# 25-Power-CPU.net
KiCad netlist of a schematic drawn in Altium Designer
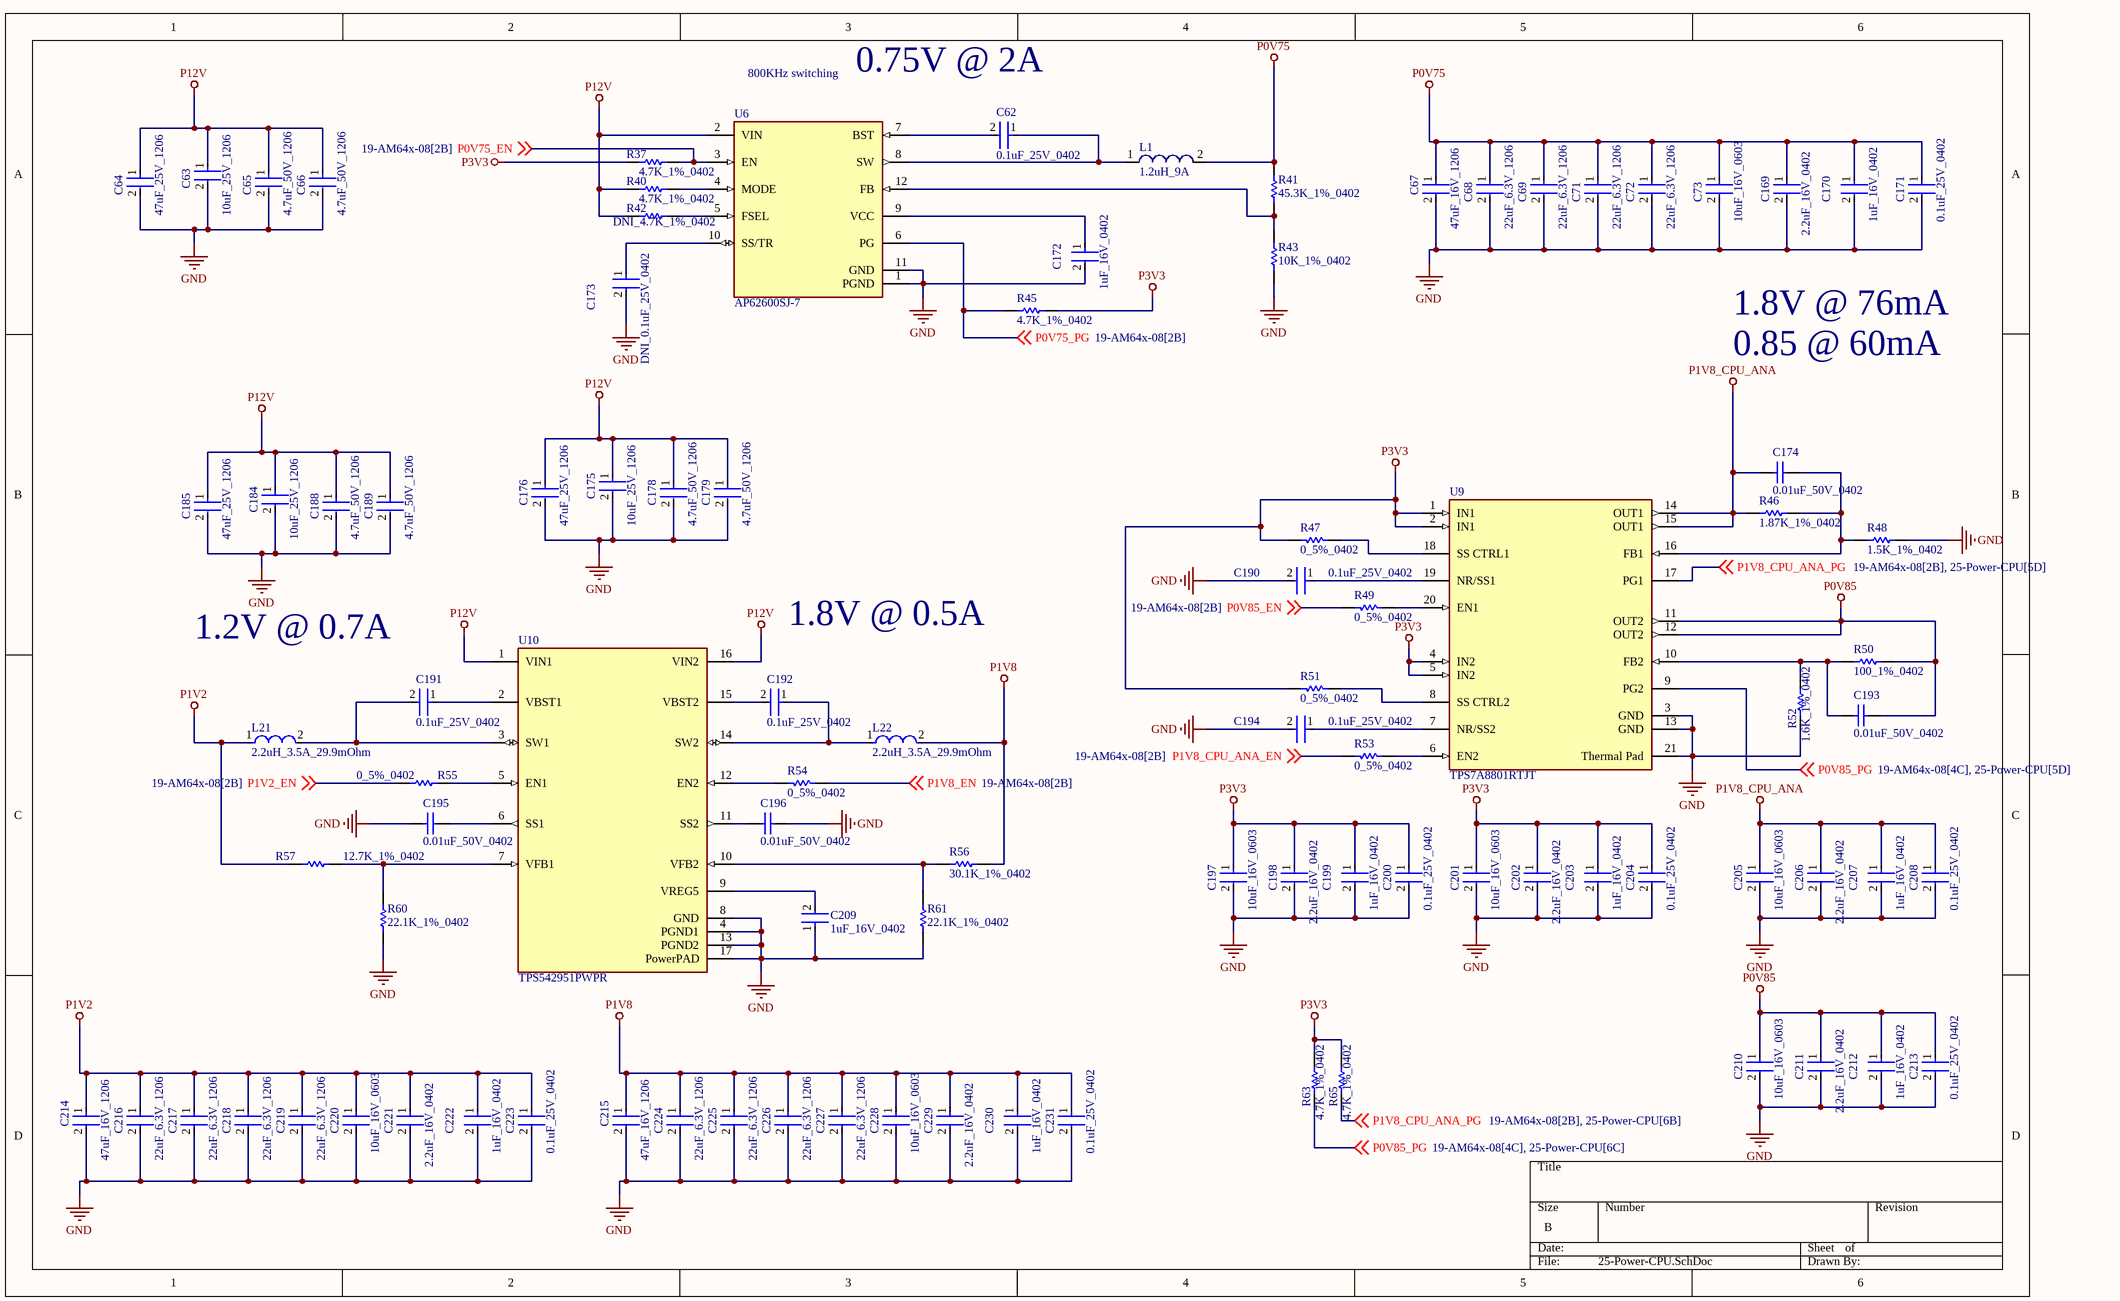
[diagram p0: 25-Power-CPU.SchDoc]

(export (version "E")
  (design (tool "Eeschema 10.0.6"))
  (components
    (comp (ref "C62")
      (value "0.1uF_25V_0402")
      (footprint "FP-0402-L_1_0_1-W_0_5_0_1-IPC_C")
      (description "General Purpose Ceramic Capacitor, 0402, 100nF, 10%, X7R, 15%, 25V")
      (fields (field (name "VOLTAGE") "25V") (field (name "TOLERANCE") "10%"))
      (libsource (lib "Altium Content Vault") (part "b4654b650e69147ec39a6b967a45e02"))
    )
    (comp (ref "C63")
      (value "10uF_25V_1206")
      (footprint "FP-1206-L_3_2_0_2-W_1_6_0-IPC_A")
      (description "General Purpose Ceramic Capacitor, 1206, 10uF, 20%, X5R, 15%, 25V")
      (fields (field (name "TOLERANCE") "20%"))
      (libsource (lib "Altium Content Vault") (part "02cd4be3c70576c341d710602a673aa"))
    )
    (comp (ref "C64")
      (value "47uF_25V_1206")
      (footprint "FP-C3216-160-0_2-MFG")
      (description "Multilayer Ceramic Capacitors 47uF ±20% 25V X5R SMD 1206")
      (fields (field (name "VOLTAGE") "25V") (field (name "TOLERANCE") "20%"))
      (libsource (lib "Altium Content Vault") (part "11868f565c42a9108669ba33697ecf6"))
    )
    (comp (ref "C65")
      (value "4.7uF_50V_1206")
      (footprint "FP-GRM31C-0_2-e0_3_0_8-IPC_C")
      (description "Chip Multilayer Ceramic Capacitors for General Purpose, 1206, 4.7uF, X7R, 15%, 10%, 50V")
      (fields (field (name "VOLTAGE") "50V") (field (name "TOLERANCE") "10%"))
      (libsource (lib "Altium Content Vault") (part "02cd4be3c70576c341d710602a673aa"))
    )
    (comp (ref "C66")
      (value "4.7uF_50V_1206")
      (footprint "FP-GRM31C-0_2-e0_3_0_8-IPC_C")
      (description "Chip Multilayer Ceramic Capacitors for General Purpose, 1206, 4.7uF, X7R, 15%, 10%, 50V")
      (fields (field (name "VOLTAGE") "50V") (field (name "TOLERANCE") "10%"))
      (libsource (lib "Altium Content Vault") (part "02cd4be3c70576c341d710602a673aa"))
    )
    (comp (ref "C67")
      (value "47uF_16V_1206")
      (footprint "FP-C3216-160-0_2-MFG")
      (description "Multilayer Ceramic Capacitors 47uF ±20% 16V X5R SMD 1206")
      (fields (field (name "TOLERANCE") "20%"))
      (libsource (lib "Altium Content Vault") (part "11868f565c42a9108669ba33697ecf6"))
    )
    (comp (ref "C68")
      (value "22uF_6.3V_1206")
      (footprint "FP-1206-L_3_2_0_2-W_1_6_0-IPC_C")
      (description "General Purpose Ceramic Capacitor, 1206, 22uF, 20%, X5R, 15%, 6.3V")
      (fields (field (name "TOLERANCE") "20%") (field (name "VOLTAGE") "6.3V"))
      (libsource (lib "Altium Content Vault") (part "02cd4be3c70576c341d710602a673aa"))
    )
    (comp (ref "C69")
      (value "22uF_6.3V_1206")
      (footprint "FP-1206-L_3_2_0_2-W_1_6_0-IPC_C")
      (description "General Purpose Ceramic Capacitor, 1206, 22uF, 20%, X5R, 15%, 6.3V")
      (fields (field (name "TOLERANCE") "20%") (field (name "VOLTAGE") "6.3V"))
      (libsource (lib "Altium Content Vault") (part "02cd4be3c70576c341d710602a673aa"))
    )
    (comp (ref "C71")
      (value "22uF_6.3V_1206")
      (footprint "FP-1206-L_3_2_0_2-W_1_6_0-IPC_C")
      (description "General Purpose Ceramic Capacitor, 1206, 22uF, 20%, X5R, 15%, 6.3V")
      (fields (field (name "TOLERANCE") "20%") (field (name "VOLTAGE") "6.3V"))
      (libsource (lib "Altium Content Vault") (part "02cd4be3c70576c341d710602a673aa"))
    )
    (comp (ref "C72")
      (value "22uF_6.3V_1206")
      (footprint "FP-1206-L_3_2_0_2-W_1_6_0-IPC_C")
      (description "General Purpose Ceramic Capacitor, 1206, 22uF, 20%, X5R, 15%, 6.3V")
      (fields (field (name "TOLERANCE") "20%") (field (name "VOLTAGE") "6.3V"))
      (libsource (lib "Altium Content Vault") (part "02cd4be3c70576c341d710602a673aa"))
    )
    (comp (ref "C73")
      (value "10uF_16V_0603")
      (footprint "FP-0603-L_1_6_0_2-W_0_8_0-MFG")
      (description "Multilayer Ceramic Capacitor 10uF 16V X5R 20% SMD 0603 T/R")
      (fields (field (name "TOLERANCE") "20%"))
      (libsource (lib "Altium Content Vault") (part "b4654b650e69147ec39a6b967a45e02"))
    )
    (comp (ref "C169")
      (value "2.2uF_16V_0402")
      (footprint "FP-C1005-050-0_05-IPC_A")
      (description "Multilayer Ceramic Capacitors 2.2μF ±10% 16V X5R SMD 0402")
      (fields (field (name "TOLERANCE") "10%"))
      (libsource (lib "Altium Content Vault") (part "b4654b650e69147ec39a6b967a45e02"))
    )
    (comp (ref "C170")
      (value "1uF_16V_0402")
      (footprint "FP-0402-L_1_0_0_05-W_0_5-IPC_A")
      (description "None")
      (fields (field (name "TOLERANCE") "10%"))
      (libsource (lib "Altium Content Vault") (part "b4654b650e69147ec39a6b967a45e02"))
    )
    (comp (ref "C171")
      (value "0.1uF_25V_0402")
      (footprint "FP-0402-L_1_0_1-W_0_5_0_1-IPC_C")
      (description "General Purpose Ceramic Capacitor, 0402, 100nF, 10%, X7R, 15%, 25V")
      (fields (field (name "VOLTAGE") "25V") (field (name "TOLERANCE") "10%"))
      (libsource (lib "Altium Content Vault") (part "b4654b650e69147ec39a6b967a45e02"))
    )
    (comp (ref "C172")
      (value "1uF_16V_0402")
      (footprint "FP-0402-L_1_0_0_05-W_0_5-IPC_A")
      (description "None")
      (fields (field (name "TOLERANCE") "10%"))
      (libsource (lib "Altium Content Vault") (part "b4654b650e69147ec39a6b967a45e02"))
    )
    (comp (ref "C173")
      (value "DNI_0.1uF_25V_0402")
      (footprint "FP-0402-L_1_0_1-W_0_5_0_1-IPC_C")
      (description "General Purpose Ceramic Capacitor, 0402, 100nF, 10%, X7R, 15%, 25V")
      (fields (field (name "VOLTAGE") "25V") (field (name "TOLERANCE") "10%"))
      (libsource (lib "Altium Content Vault") (part "b4654b650e69147ec39a6b967a45e02"))
    )
    (comp (ref "C174")
      (value "0.01uF_50V_0402")
      (footprint "CAPC1005X55X30LL05T10")
      (fields (field (name "PART NUMBER") "C0402C103K5RACTU") (field (name "MANUFACTURER") "Kemet"))
      (libsource (lib "Altium Content Vault") (part "CAP"))
    )
    (comp (ref "C175")
      (value "10uF_25V_1206")
      (footprint "FP-1206-L_3_2_0_2-W_1_6_0-IPC_A")
      (description "General Purpose Ceramic Capacitor, 1206, 10uF, 20%, X5R, 15%, 25V")
      (fields (field (name "TOLERANCE") "20%"))
      (libsource (lib "Altium Content Vault") (part "02cd4be3c70576c341d710602a673aa"))
    )
    (comp (ref "C176")
      (value "47uF_25V_1206")
      (footprint "FP-C3216-160-0_2-MFG")
      (description "Multilayer Ceramic Capacitors 47uF ±20% 25V X5R SMD 1206")
      (fields (field (name "VOLTAGE") "25V") (field (name "TOLERANCE") "20%"))
      (libsource (lib "Altium Content Vault") (part "11868f565c42a9108669ba33697ecf6"))
    )
    (comp (ref "C178")
      (value "4.7uF_50V_1206")
      (footprint "FP-GRM31C-0_2-e0_3_0_8-IPC_C")
      (description "Chip Multilayer Ceramic Capacitors for General Purpose, 1206, 4.7uF, X7R, 15%, 10%, 50V")
      (fields (field (name "VOLTAGE") "50V") (field (name "TOLERANCE") "10%"))
      (libsource (lib "Altium Content Vault") (part "02cd4be3c70576c341d710602a673aa"))
    )
    (comp (ref "C179")
      (value "4.7uF_50V_1206")
      (footprint "FP-GRM31C-0_2-e0_3_0_8-IPC_C")
      (description "Chip Multilayer Ceramic Capacitors for General Purpose, 1206, 4.7uF, X7R, 15%, 10%, 50V")
      (fields (field (name "VOLTAGE") "50V") (field (name "TOLERANCE") "10%"))
      (libsource (lib "Altium Content Vault") (part "02cd4be3c70576c341d710602a673aa"))
    )
    (comp (ref "C184")
      (value "10uF_25V_1206")
      (footprint "FP-1206-L_3_2_0_2-W_1_6_0-IPC_A")
      (description "General Purpose Ceramic Capacitor, 1206, 10uF, 20%, X5R, 15%, 25V")
      (fields (field (name "TOLERANCE") "20%"))
      (libsource (lib "Altium Content Vault") (part "02cd4be3c70576c341d710602a673aa"))
    )
    (comp (ref "C185")
      (value "47uF_25V_1206")
      (footprint "FP-C3216-160-0_2-MFG")
      (description "Multilayer Ceramic Capacitors 47uF ±20% 25V X5R SMD 1206")
      (fields (field (name "VOLTAGE") "25V") (field (name "TOLERANCE") "20%"))
      (libsource (lib "Altium Content Vault") (part "11868f565c42a9108669ba33697ecf6"))
    )
    (comp (ref "C188")
      (value "4.7uF_50V_1206")
      (footprint "FP-GRM31C-0_2-e0_3_0_8-IPC_C")
      (description "Chip Multilayer Ceramic Capacitors for General Purpose, 1206, 4.7uF, X7R, 15%, 10%, 50V")
      (fields (field (name "VOLTAGE") "50V") (field (name "TOLERANCE") "10%"))
      (libsource (lib "Altium Content Vault") (part "02cd4be3c70576c341d710602a673aa"))
    )
    (comp (ref "C189")
      (value "4.7uF_50V_1206")
      (footprint "FP-GRM31C-0_2-e0_3_0_8-IPC_C")
      (description "Chip Multilayer Ceramic Capacitors for General Purpose, 1206, 4.7uF, X7R, 15%, 10%, 50V")
      (fields (field (name "VOLTAGE") "50V") (field (name "TOLERANCE") "10%"))
      (libsource (lib "Altium Content Vault") (part "02cd4be3c70576c341d710602a673aa"))
    )
    (comp (ref "C190")
      (value "0.1uF_25V_0402")
      (footprint "FP-0402-L_1_0_1-W_0_5_0_1-IPC_C")
      (description "General Purpose Ceramic Capacitor, 0402, 100nF, 10%, X7R, 15%, 25V")
      (fields (field (name "VOLTAGE") "25V") (field (name "TOLERANCE") "10%"))
      (libsource (lib "Altium Content Vault") (part "b4654b650e69147ec39a6b967a45e02"))
    )
    (comp (ref "C191")
      (value "0.1uF_25V_0402")
      (footprint "FP-0402-L_1_0_1-W_0_5_0_1-IPC_C")
      (description "General Purpose Ceramic Capacitor, 0402, 100nF, 10%, X7R, 15%, 25V")
      (fields (field (name "VOLTAGE") "25V") (field (name "TOLERANCE") "10%"))
      (libsource (lib "Altium Content Vault") (part "b4654b650e69147ec39a6b967a45e02"))
    )
    (comp (ref "C192")
      (value "0.1uF_25V_0402")
      (footprint "FP-0402-L_1_0_1-W_0_5_0_1-IPC_C")
      (description "General Purpose Ceramic Capacitor, 0402, 100nF, 10%, X7R, 15%, 25V")
      (fields (field (name "VOLTAGE") "25V") (field (name "TOLERANCE") "10%"))
      (libsource (lib "Altium Content Vault") (part "b4654b650e69147ec39a6b967a45e02"))
    )
    (comp (ref "C193")
      (value "0.01uF_50V_0402")
      (footprint "CAPC1005X55X30LL05T10")
      (fields (field (name "PART NUMBER") "C0402C103K5RACTU") (field (name "MANUFACTURER") "Kemet"))
      (libsource (lib "Altium Content Vault") (part "CAP"))
    )
    (comp (ref "C194")
      (value "0.1uF_25V_0402")
      (footprint "FP-0402-L_1_0_1-W_0_5_0_1-IPC_C")
      (description "General Purpose Ceramic Capacitor, 0402, 100nF, 10%, X7R, 15%, 25V")
      (fields (field (name "VOLTAGE") "25V") (field (name "TOLERANCE") "10%"))
      (libsource (lib "Altium Content Vault") (part "b4654b650e69147ec39a6b967a45e02"))
    )
    (comp (ref "C195")
      (value "0.01uF_50V_0402")
      (footprint "CAPC1005X55X30LL05T10")
      (fields (field (name "PART NUMBER") "C0402C103K5RACTU") (field (name "MANUFACTURER") "Kemet"))
      (libsource (lib "Altium Content Vault") (part "CAP"))
    )
    (comp (ref "C196")
      (value "0.01uF_50V_0402")
      (footprint "CAPC1005X55X30LL05T10")
      (fields (field (name "PART NUMBER") "C0402C103K5RACTU") (field (name "MANUFACTURER") "Kemet"))
      (libsource (lib "Altium Content Vault") (part "CAP"))
    )
    (comp (ref "C197")
      (value "10uF_16V_0603")
      (footprint "FP-0603-L_1_6_0_2-W_0_8_0-MFG")
      (description "Multilayer Ceramic Capacitor 10uF 16V X5R 20% SMD 0603 T/R")
      (fields (field (name "TOLERANCE") "20%"))
      (libsource (lib "Altium Content Vault") (part "b4654b650e69147ec39a6b967a45e02"))
    )
    (comp (ref "C198")
      (value "2.2uF_16V_0402")
      (footprint "FP-C1005-050-0_05-IPC_A")
      (description "Multilayer Ceramic Capacitors 2.2μF ±10% 16V X5R SMD 0402")
      (fields (field (name "TOLERANCE") "10%"))
      (libsource (lib "Altium Content Vault") (part "b4654b650e69147ec39a6b967a45e02"))
    )
    (comp (ref "C199")
      (value "1uF_16V_0402")
      (footprint "FP-0402-L_1_0_0_05-W_0_5-IPC_A")
      (description "None")
      (fields (field (name "TOLERANCE") "10%"))
      (libsource (lib "Altium Content Vault") (part "b4654b650e69147ec39a6b967a45e02"))
    )
    (comp (ref "C200")
      (value "0.1uF_25V_0402")
      (footprint "FP-0402-L_1_0_1-W_0_5_0_1-IPC_C")
      (description "General Purpose Ceramic Capacitor, 0402, 100nF, 10%, X7R, 15%, 25V")
      (fields (field (name "VOLTAGE") "25V") (field (name "TOLERANCE") "10%"))
      (libsource (lib "Altium Content Vault") (part "b4654b650e69147ec39a6b967a45e02"))
    )
    (comp (ref "C201")
      (value "10uF_16V_0603")
      (footprint "FP-0603-L_1_6_0_2-W_0_8_0-MFG")
      (description "Multilayer Ceramic Capacitor 10uF 16V X5R 20% SMD 0603 T/R")
      (fields (field (name "TOLERANCE") "20%"))
      (libsource (lib "Altium Content Vault") (part "b4654b650e69147ec39a6b967a45e02"))
    )
    (comp (ref "C202")
      (value "2.2uF_16V_0402")
      (footprint "FP-C1005-050-0_05-IPC_A")
      (description "Multilayer Ceramic Capacitors 2.2μF ±10% 16V X5R SMD 0402")
      (fields (field (name "TOLERANCE") "10%"))
      (libsource (lib "Altium Content Vault") (part "b4654b650e69147ec39a6b967a45e02"))
    )
    (comp (ref "C203")
      (value "1uF_16V_0402")
      (footprint "FP-0402-L_1_0_0_05-W_0_5-IPC_A")
      (description "None")
      (fields (field (name "TOLERANCE") "10%"))
      (libsource (lib "Altium Content Vault") (part "b4654b650e69147ec39a6b967a45e02"))
    )
    (comp (ref "C204")
      (value "0.1uF_25V_0402")
      (footprint "FP-0402-L_1_0_1-W_0_5_0_1-IPC_C")
      (description "General Purpose Ceramic Capacitor, 0402, 100nF, 10%, X7R, 15%, 25V")
      (fields (field (name "VOLTAGE") "25V") (field (name "TOLERANCE") "10%"))
      (libsource (lib "Altium Content Vault") (part "b4654b650e69147ec39a6b967a45e02"))
    )
    (comp (ref "C205")
      (value "10uF_16V_0603")
      (footprint "FP-0603-L_1_6_0_2-W_0_8_0-MFG")
      (description "Multilayer Ceramic Capacitor 10uF 16V X5R 20% SMD 0603 T/R")
      (fields (field (name "TOLERANCE") "20%"))
      (libsource (lib "Altium Content Vault") (part "b4654b650e69147ec39a6b967a45e02"))
    )
    (comp (ref "C206")
      (value "2.2uF_16V_0402")
      (footprint "FP-C1005-050-0_05-IPC_A")
      (description "Multilayer Ceramic Capacitors 2.2μF ±10% 16V X5R SMD 0402")
      (fields (field (name "TOLERANCE") "10%"))
      (libsource (lib "Altium Content Vault") (part "b4654b650e69147ec39a6b967a45e02"))
    )
    (comp (ref "C207")
      (value "1uF_16V_0402")
      (footprint "FP-0402-L_1_0_0_05-W_0_5-IPC_A")
      (description "None")
      (fields (field (name "TOLERANCE") "10%"))
      (libsource (lib "Altium Content Vault") (part "b4654b650e69147ec39a6b967a45e02"))
    )
    (comp (ref "C208")
      (value "0.1uF_25V_0402")
      (footprint "FP-0402-L_1_0_1-W_0_5_0_1-IPC_C")
      (description "General Purpose Ceramic Capacitor, 0402, 100nF, 10%, X7R, 15%, 25V")
      (fields (field (name "VOLTAGE") "25V") (field (name "TOLERANCE") "10%"))
      (libsource (lib "Altium Content Vault") (part "b4654b650e69147ec39a6b967a45e02"))
    )
    (comp (ref "C209")
      (value "1uF_16V_0402")
      (footprint "FP-0402-L_1_0_0_05-W_0_5-IPC_A")
      (description "None")
      (fields (field (name "TOLERANCE") "10%"))
      (libsource (lib "Altium Content Vault") (part "b4654b650e69147ec39a6b967a45e02"))
    )
    (comp (ref "C210")
      (value "10uF_16V_0603")
      (footprint "FP-0603-L_1_6_0_2-W_0_8_0-MFG")
      (description "Multilayer Ceramic Capacitor 10uF 16V X5R 20% SMD 0603 T/R")
      (fields (field (name "TOLERANCE") "20%"))
      (libsource (lib "Altium Content Vault") (part "b4654b650e69147ec39a6b967a45e02"))
    )
    (comp (ref "C211")
      (value "2.2uF_16V_0402")
      (footprint "FP-C1005-050-0_05-IPC_A")
      (description "Multilayer Ceramic Capacitors 2.2μF ±10% 16V X5R SMD 0402")
      (fields (field (name "TOLERANCE") "10%"))
      (libsource (lib "Altium Content Vault") (part "b4654b650e69147ec39a6b967a45e02"))
    )
    (comp (ref "C212")
      (value "1uF_16V_0402")
      (footprint "FP-0402-L_1_0_0_05-W_0_5-IPC_A")
      (description "None")
      (fields (field (name "TOLERANCE") "10%"))
      (libsource (lib "Altium Content Vault") (part "b4654b650e69147ec39a6b967a45e02"))
    )
    (comp (ref "C213")
      (value "0.1uF_25V_0402")
      (footprint "FP-0402-L_1_0_1-W_0_5_0_1-IPC_C")
      (description "General Purpose Ceramic Capacitor, 0402, 100nF, 10%, X7R, 15%, 25V")
      (fields (field (name "VOLTAGE") "25V") (field (name "TOLERANCE") "10%"))
      (libsource (lib "Altium Content Vault") (part "b4654b650e69147ec39a6b967a45e02"))
    )
    (comp (ref "C214")
      (value "47uF_16V_1206")
      (footprint "FP-C3216-160-0_2-MFG")
      (description "Multilayer Ceramic Capacitors 47uF ±20% 16V X5R SMD 1206")
      (fields (field (name "TOLERANCE") "20%"))
      (libsource (lib "Altium Content Vault") (part "11868f565c42a9108669ba33697ecf6"))
    )
    (comp (ref "C215")
      (value "47uF_16V_1206")
      (footprint "FP-C3216-160-0_2-MFG")
      (description "Multilayer Ceramic Capacitors 47uF ±20% 16V X5R SMD 1206")
      (fields (field (name "TOLERANCE") "20%"))
      (libsource (lib "Altium Content Vault") (part "11868f565c42a9108669ba33697ecf6"))
    )
    (comp (ref "C216")
      (value "22uF_6.3V_1206")
      (footprint "FP-1206-L_3_2_0_2-W_1_6_0-IPC_C")
      (description "General Purpose Ceramic Capacitor, 1206, 22uF, 20%, X5R, 15%, 6.3V")
      (fields (field (name "TOLERANCE") "20%") (field (name "VOLTAGE") "6.3V"))
      (libsource (lib "Altium Content Vault") (part "02cd4be3c70576c341d710602a673aa"))
    )
    (comp (ref "C217")
      (value "22uF_6.3V_1206")
      (footprint "FP-1206-L_3_2_0_2-W_1_6_0-IPC_C")
      (description "General Purpose Ceramic Capacitor, 1206, 22uF, 20%, X5R, 15%, 6.3V")
      (fields (field (name "TOLERANCE") "20%") (field (name "VOLTAGE") "6.3V"))
      (libsource (lib "Altium Content Vault") (part "02cd4be3c70576c341d710602a673aa"))
    )
    (comp (ref "C218")
      (value "22uF_6.3V_1206")
      (footprint "FP-1206-L_3_2_0_2-W_1_6_0-IPC_C")
      (description "General Purpose Ceramic Capacitor, 1206, 22uF, 20%, X5R, 15%, 6.3V")
      (fields (field (name "TOLERANCE") "20%") (field (name "VOLTAGE") "6.3V"))
      (libsource (lib "Altium Content Vault") (part "02cd4be3c70576c341d710602a673aa"))
    )
    (comp (ref "C219")
      (value "22uF_6.3V_1206")
      (footprint "FP-1206-L_3_2_0_2-W_1_6_0-IPC_C")
      (description "General Purpose Ceramic Capacitor, 1206, 22uF, 20%, X5R, 15%, 6.3V")
      (fields (field (name "TOLERANCE") "20%") (field (name "VOLTAGE") "6.3V"))
      (libsource (lib "Altium Content Vault") (part "02cd4be3c70576c341d710602a673aa"))
    )
    (comp (ref "C220")
      (value "10uF_16V_0603")
      (footprint "FP-0603-L_1_6_0_2-W_0_8_0-MFG")
      (description "Multilayer Ceramic Capacitor 10uF 16V X5R 20% SMD 0603 T/R")
      (fields (field (name "TOLERANCE") "20%"))
      (libsource (lib "Altium Content Vault") (part "b4654b650e69147ec39a6b967a45e02"))
    )
    (comp (ref "C221")
      (value "2.2uF_16V_0402")
      (footprint "FP-C1005-050-0_05-IPC_A")
      (description "Multilayer Ceramic Capacitors 2.2μF ±10% 16V X5R SMD 0402")
      (fields (field (name "TOLERANCE") "10%"))
      (libsource (lib "Altium Content Vault") (part "b4654b650e69147ec39a6b967a45e02"))
    )
    (comp (ref "C222")
      (value "1uF_16V_0402")
      (footprint "FP-0402-L_1_0_0_05-W_0_5-IPC_A")
      (description "None")
      (fields (field (name "TOLERANCE") "10%"))
      (libsource (lib "Altium Content Vault") (part "b4654b650e69147ec39a6b967a45e02"))
    )
    (comp (ref "C223")
      (value "0.1uF_25V_0402")
      (footprint "FP-0402-L_1_0_1-W_0_5_0_1-IPC_C")
      (description "General Purpose Ceramic Capacitor, 0402, 100nF, 10%, X7R, 15%, 25V")
      (fields (field (name "VOLTAGE") "25V") (field (name "TOLERANCE") "10%"))
      (libsource (lib "Altium Content Vault") (part "b4654b650e69147ec39a6b967a45e02"))
    )
    (comp (ref "C224")
      (value "22uF_6.3V_1206")
      (footprint "FP-1206-L_3_2_0_2-W_1_6_0-IPC_C")
      (description "General Purpose Ceramic Capacitor, 1206, 22uF, 20%, X5R, 15%, 6.3V")
      (fields (field (name "TOLERANCE") "20%") (field (name "VOLTAGE") "6.3V"))
      (libsource (lib "Altium Content Vault") (part "02cd4be3c70576c341d710602a673aa"))
    )
    (comp (ref "C225")
      (value "22uF_6.3V_1206")
      (footprint "FP-1206-L_3_2_0_2-W_1_6_0-IPC_C")
      (description "General Purpose Ceramic Capacitor, 1206, 22uF, 20%, X5R, 15%, 6.3V")
      (fields (field (name "TOLERANCE") "20%") (field (name "VOLTAGE") "6.3V"))
      (libsource (lib "Altium Content Vault") (part "02cd4be3c70576c341d710602a673aa"))
    )
    (comp (ref "C226")
      (value "22uF_6.3V_1206")
      (footprint "FP-1206-L_3_2_0_2-W_1_6_0-IPC_C")
      (description "General Purpose Ceramic Capacitor, 1206, 22uF, 20%, X5R, 15%, 6.3V")
      (fields (field (name "TOLERANCE") "20%") (field (name "VOLTAGE") "6.3V"))
      (libsource (lib "Altium Content Vault") (part "02cd4be3c70576c341d710602a673aa"))
    )
    (comp (ref "C227")
      (value "22uF_6.3V_1206")
      (footprint "FP-1206-L_3_2_0_2-W_1_6_0-IPC_C")
      (description "General Purpose Ceramic Capacitor, 1206, 22uF, 20%, X5R, 15%, 6.3V")
      (fields (field (name "TOLERANCE") "20%") (field (name "VOLTAGE") "6.3V"))
      (libsource (lib "Altium Content Vault") (part "02cd4be3c70576c341d710602a673aa"))
    )
    (comp (ref "C228")
      (value "10uF_16V_0603")
      (footprint "FP-0603-L_1_6_0_2-W_0_8_0-MFG")
      (description "Multilayer Ceramic Capacitor 10uF 16V X5R 20% SMD 0603 T/R")
      (fields (field (name "TOLERANCE") "20%"))
      (libsource (lib "Altium Content Vault") (part "b4654b650e69147ec39a6b967a45e02"))
    )
    (comp (ref "C229")
      (value "2.2uF_16V_0402")
      (footprint "FP-C1005-050-0_05-IPC_A")
      (description "Multilayer Ceramic Capacitors 2.2μF ±10% 16V X5R SMD 0402")
      (fields (field (name "TOLERANCE") "10%"))
      (libsource (lib "Altium Content Vault") (part "b4654b650e69147ec39a6b967a45e02"))
    )
    (comp (ref "C230")
      (value "1uF_16V_0402")
      (footprint "FP-0402-L_1_0_0_05-W_0_5-IPC_A")
      (description "None")
      (fields (field (name "TOLERANCE") "10%"))
      (libsource (lib "Altium Content Vault") (part "b4654b650e69147ec39a6b967a45e02"))
    )
    (comp (ref "C231")
      (value "0.1uF_25V_0402")
      (footprint "FP-0402-L_1_0_1-W_0_5_0_1-IPC_C")
      (description "General Purpose Ceramic Capacitor, 0402, 100nF, 10%, X7R, 15%, 25V")
      (fields (field (name "VOLTAGE") "25V") (field (name "TOLERANCE") "10%"))
      (libsource (lib "Altium Content Vault") (part "b4654b650e69147ec39a6b967a45e02"))
    )
    (comp (ref "L1")
      (value "1.2uH_9A")
      (footprint "WE-LHMI 7050")
      (description "SMD Power Inductor WE-LHMI, L=1.2 µH")
      (fields (field (name "MANUFACTURER") "Wuerth Elektronik") (field (name "PARTNUMBER") "74437349012"))
      (libsource (lib "Altium Content Vault") (part "WE-IND-INDUCTOR-2"))
    )
    (comp (ref "L21")
      (value "2.2uH_3.5A_29.9mOhm")
      (footprint "FP-NRS5030-H_3_1-MFG")
      (description "Inductor Power Shielded Wirewound 2.2uH 30% 100KHz Ferrite 3.5A 29.9mΩ DCR Automotive T/R")
      (fields (field (name "TOLERANCE") "30%"))
      (libsource (lib "Altium Content Vault") (part "725321dda6339637d4d059423bc1c3c"))
    )
    (comp (ref "L22")
      (value "2.2uH_3.5A_29.9mOhm")
      (footprint "FP-NRS5030-H_3_1-MFG")
      (description "Inductor Power Shielded Wirewound 2.2uH 30% 100KHz Ferrite 3.5A 29.9mΩ DCR Automotive T/R")
      (fields (field (name "TOLERANCE") "30%"))
      (libsource (lib "Altium Content Vault") (part "725321dda6339637d4d059423bc1c3c"))
    )
    (comp (ref "R37")
      (value "4.7K_1%_0402")
      (footprint "RESC1005X40X25NL10T10")
      (fields (field (name "MANUFACTURER") "Bourns") (field (name "PART NUMBER") "CR0402-FX-4701GLF"))
      (libsource (lib "Altium Content Vault") (part "RES"))
    )
    (comp (ref "R40")
      (value "4.7K_1%_0402")
      (footprint "RESC1005X40X25NL10T10")
      (fields (field (name "MANUFACTURER") "Bourns") (field (name "PART NUMBER") "CR0402-FX-4701GLF"))
      (libsource (lib "Altium Content Vault") (part "RES"))
    )
    (comp (ref "R41")
      (value "45.3K_1%_0402")
      (footprint "RESC1005X40X25ML05T10")
      (fields (field (name "PART NUMBER") "RC0402FR-0745K3L") (field (name "MANUFACTURER") "Yageo / Phycomp"))
      (libsource (lib "Altium Content Vault") (part "RES"))
    )
    (comp (ref "R42")
      (value "DNI_4.7K_1%_0402")
      (footprint "RESC1005X40X25NL10T10")
      (fields (field (name "MANUFACTURER") "Bourns") (field (name "PART NUMBER") "CR0402-FX-4701GLF"))
      (libsource (lib "Altium Content Vault") (part "RES"))
    )
    (comp (ref "R43")
      (value "10K_1%_0402")
      (footprint "RESC1005X40X25NL10T10")
      (fields (field (name "MANUFACTURER") "Bourns") (field (name "PART NUMBER") "CR0402-FX-1002GLF"))
      (libsource (lib "Altium Content Vault") (part "RES"))
    )
    (comp (ref "R45")
      (value "4.7K_1%_0402")
      (footprint "RESC1005X40X25NL10T10")
      (fields (field (name "MANUFACTURER") "Bourns") (field (name "PART NUMBER") "CR0402-FX-4701GLF"))
      (libsource (lib "Altium Content Vault") (part "RES"))
    )
    (comp (ref "R46")
      (value "1.87K_1%_0402")
      (footprint "RESC1005X40X25ML05T05")
      (fields (field (name "MANUFACTURER") "Panasonic") (field (name "PART NUMBER") "ERJ-2RKF1871X"))
      (libsource (lib "Altium Content Vault") (part "RES"))
    )
    (comp (ref "R47")
      (value "0_5%_0402")
      (footprint "RESC1005X40X25LL10T10")
      (fields (field (name "MANUFACTURER") "KOA Speer") (field (name "PART NUMBER") "RK73Z1ETTP"))
      (libsource (lib "Altium Content Vault") (part "RES"))
    )
    (comp (ref "R48")
      (value "1.5K_1%_0402")
      (footprint "RESC1005X40X25NL05T10")
      (fields (field (name "PART NUMBER") "ERJ-U02F1501X") (field (name "MANUFACTURER") "Panasonic"))
      (libsource (lib "Altium Content Vault") (part "RES"))
    )
    (comp (ref "R49")
      (value "0_5%_0402")
      (footprint "RESC1005X40X25LL10T10")
      (fields (field (name "MANUFACTURER") "KOA Speer") (field (name "PART NUMBER") "RK73Z1ETTP"))
      (libsource (lib "Altium Content Vault") (part "RES"))
    )
    (comp (ref "R50")
      (value "100_1%_0402")
      (footprint "RESC1005X40X25ML05T10")
      (fields (field (name "PART NUMBER") "ERJ-U02F1000X") (field (name "MANUFACTURER") "Panasonic"))
      (libsource (lib "Altium Content Vault") (part "RES"))
    )
    (comp (ref "R51")
      (value "0_5%_0402")
      (footprint "RESC1005X40X25LL10T10")
      (fields (field (name "MANUFACTURER") "KOA Speer") (field (name "PART NUMBER") "RK73Z1ETTP"))
      (libsource (lib "Altium Content Vault") (part "RES"))
    )
    (comp (ref "R52")
      (value "1.6K_1%_0402")
      (footprint "RESC1005X40X25LL05T05")
      (fields (field (name "MANUFACTURER") "Panasonic") (field (name "PART NUMBER") "ERJ-2RKF1601X"))
      (libsource (lib "Altium Content Vault") (part "RES"))
    )
    (comp (ref "R53")
      (value "0_5%_0402")
      (footprint "RESC1005X40X25LL10T10")
      (fields (field (name "MANUFACTURER") "KOA Speer") (field (name "PART NUMBER") "RK73Z1ETTP"))
      (libsource (lib "Altium Content Vault") (part "RES"))
    )
    (comp (ref "R54")
      (value "0_5%_0402")
      (footprint "RESC1005X40X25LL10T10")
      (fields (field (name "MANUFACTURER") "KOA Speer") (field (name "PART NUMBER") "RK73Z1ETTP"))
      (libsource (lib "Altium Content Vault") (part "RES"))
    )
    (comp (ref "R55")
      (value "0_5%_0402")
      (footprint "RESC1005X40X25LL10T10")
      (fields (field (name "MANUFACTURER") "KOA Speer") (field (name "PART NUMBER") "RK73Z1ETTP"))
      (libsource (lib "Altium Content Vault") (part "RES"))
    )
    (comp (ref "R56")
      (value "30.1K_1%_0402")
      (footprint "RESC1005X40X25NL10T10")
      (fields (field (name "MANUFACTURER") "KOA Speer") (field (name "PART NUMBER") "RK73H1ETTP3012F"))
      (libsource (lib "Altium Content Vault") (part "RES"))
    )
    (comp (ref "R57")
      (value "12.7K_1%_0402")
      (footprint "RESC1005X40X25LL05T05")
      (fields (field (name "MANUFACTURER") "Panasonic") (field (name "PART NUMBER") "ERJ-2RKF1272X"))
      (libsource (lib "Altium Content Vault") (part "RES"))
    )
    (comp (ref "R60")
      (value "22.1K_1%_0402")
      (footprint "RESC1005X40X25NL10T10")
      (fields (field (name "MANUFACTURER") "KOA Speer") (field (name "PART NUMBER") "RK73H1ETTP2212F"))
      (libsource (lib "Altium Content Vault") (part "RES"))
    )
    (comp (ref "R61")
      (value "22.1K_1%_0402")
      (footprint "RESC1005X40X25NL10T10")
      (fields (field (name "MANUFACTURER") "KOA Speer") (field (name "PART NUMBER") "RK73H1ETTP2212F"))
      (libsource (lib "Altium Content Vault") (part "RES"))
    )
    (comp (ref "R63")
      (value "4.7K_1%_0402")
      (footprint "RESC1005X40X25NL10T10")
      (fields (field (name "MANUFACTURER") "Bourns") (field (name "PART NUMBER") "CR0402-FX-4701GLF"))
      (libsource (lib "Altium Content Vault") (part "RES"))
    )
    (comp (ref "R65")
      (value "4.7K_1%_0402")
      (footprint "RESC1005X40X25NL10T10")
      (fields (field (name "MANUFACTURER") "Bourns") (field (name "PART NUMBER") "CR0402-FX-4701GLF"))
      (libsource (lib "Altium Content Vault") (part "RES"))
    )
    (comp (ref "U6")
      (value "AP62600SJ-7")
      (footprint "FP-V-QFN2030-12_Type_A-MFG")
      (description "DCDC CONV HV BUCK,V-QFN2030-12")
      (libsource (lib "Altium Content Vault") (part "03c86ce2703f4b33b3045e94f7be521"))
    )
    (comp (ref "U9")
      (value "TPS7A8801RTJT")
      (footprint "FP-RTJ0020D-MFG")
      (description "IC REG LINEAR POS ADJ 1A 20QFN")
      (fields
        (field (name "OCTOPART") "https://octopart.com/tps7a8801rtjt-texas+instruments-68059618")
        (field (name "MANUFACTURER") "Texas Instruments")
      )
      (libsource (lib "Altium Content Vault") (part "bc238ff72c2b78fce3582f75cfaf3c3"))
    )
    (comp (ref "U10")
      (value "TPS542951PWPR")
      (footprint "FP-PWP0016K-IPC_C")
      (description "IC REG BCK ADJ 2A/3A DL 16HTSSOP")
      (libsource (lib "Altium Content Vault") (part "f19ce9d0a08a933d55ca68b6efc25d5"))
    )
  )
  (nets
    (net (code "1") (name "GND") (class "Default")
      (node (ref "C169") (pin "2") (pinfunction "2_2") (pintype "passive"))
      (node (ref "C170") (pin "2") (pinfunction "2_2") (pintype "passive"))
      (node (ref "C171") (pin "2") (pinfunction "2_2") (pintype "passive"))
      (node (ref "C172") (pin "2") (pinfunction "2_2") (pintype "passive"))
      (node (ref "C173") (pin "2") (pinfunction "2_2") (pintype "passive"))
      (node (ref "C175") (pin "2") (pinfunction "2_2") (pintype "passive"))
      (node (ref "C176") (pin "2") (pinfunction "2_2") (pintype "passive"))
      (node (ref "C178") (pin "2") (pinfunction "2_2") (pintype "passive"))
      (node (ref "C179") (pin "2") (pinfunction "2_2") (pintype "passive"))
      (node (ref "C184") (pin "2") (pinfunction "2_2") (pintype "passive"))
      (node (ref "C185") (pin "2") (pinfunction "2_2") (pintype "passive"))
      (node (ref "C188") (pin "2") (pinfunction "2_2") (pintype "passive"))
      (node (ref "C189") (pin "2") (pinfunction "2_2") (pintype "passive"))
      (node (ref "C190") (pin "2") (pinfunction "2_2") (pintype "passive"))
      (node (ref "C194") (pin "2") (pinfunction "2_2") (pintype "passive"))
      (node (ref "C195") (pin "1") (pinfunction "1_1") (pintype "passive"))
      (node (ref "C196") (pin "2") (pinfunction "2_2") (pintype "passive"))
      (node (ref "C197") (pin "2") (pinfunction "2_2") (pintype "passive"))
      (node (ref "C198") (pin "2") (pinfunction "2_2") (pintype "passive"))
      (node (ref "C199") (pin "2") (pinfunction "2_2") (pintype "passive"))
      (node (ref "C200") (pin "2") (pinfunction "2_2") (pintype "passive"))
      (node (ref "C201") (pin "2") (pinfunction "2_2") (pintype "passive"))
      (node (ref "C202") (pin "2") (pinfunction "2_2") (pintype "passive"))
      (node (ref "C203") (pin "2") (pinfunction "2_2") (pintype "passive"))
      (node (ref "C204") (pin "2") (pinfunction "2_2") (pintype "passive"))
      (node (ref "C205") (pin "2") (pinfunction "2_2") (pintype "passive"))
      (node (ref "C206") (pin "2") (pinfunction "2_2") (pintype "passive"))
      (node (ref "C207") (pin "2") (pinfunction "2_2") (pintype "passive"))
      (node (ref "C208") (pin "2") (pinfunction "2_2") (pintype "passive"))
      (node (ref "C209") (pin "1") (pinfunction "1_1") (pintype "passive"))
      (node (ref "C210") (pin "2") (pinfunction "2_2") (pintype "passive"))
      (node (ref "C211") (pin "2") (pinfunction "2_2") (pintype "passive"))
      (node (ref "C212") (pin "2") (pinfunction "2_2") (pintype "passive"))
      (node (ref "C213") (pin "2") (pinfunction "2_2") (pintype "passive"))
      (node (ref "C214") (pin "2") (pinfunction "2_2") (pintype "passive"))
      (node (ref "C215") (pin "2") (pinfunction "2_2") (pintype "passive"))
      (node (ref "C216") (pin "2") (pinfunction "2_2") (pintype "passive"))
      (node (ref "C217") (pin "2") (pinfunction "2_2") (pintype "passive"))
      (node (ref "C218") (pin "2") (pinfunction "2_2") (pintype "passive"))
      (node (ref "C219") (pin "2") (pinfunction "2_2") (pintype "passive"))
      (node (ref "C220") (pin "2") (pinfunction "2_2") (pintype "passive"))
      (node (ref "C221") (pin "2") (pinfunction "2_2") (pintype "passive"))
      (node (ref "C222") (pin "2") (pinfunction "2_2") (pintype "passive"))
      (node (ref "C223") (pin "2") (pinfunction "2_2") (pintype "passive"))
      (node (ref "C224") (pin "2") (pinfunction "2_2") (pintype "passive"))
      (node (ref "C225") (pin "2") (pinfunction "2_2") (pintype "passive"))
      (node (ref "C226") (pin "2") (pinfunction "2_2") (pintype "passive"))
      (node (ref "C227") (pin "2") (pinfunction "2_2") (pintype "passive"))
      (node (ref "C228") (pin "2") (pinfunction "2_2") (pintype "passive"))
      (node (ref "C229") (pin "2") (pinfunction "2_2") (pintype "passive"))
      (node (ref "C230") (pin "2") (pinfunction "2_2") (pintype "passive"))
      (node (ref "C231") (pin "2") (pinfunction "2_2") (pintype "passive"))
      (node (ref "C63") (pin "2") (pinfunction "2_2") (pintype "passive"))
      (node (ref "C64") (pin "2") (pinfunction "2_2") (pintype "passive"))
      (node (ref "C65") (pin "2") (pinfunction "2_2") (pintype "passive"))
      (node (ref "C66") (pin "2") (pinfunction "2_2") (pintype "passive"))
      (node (ref "C67") (pin "2") (pinfunction "2_2") (pintype "passive"))
      (node (ref "C68") (pin "2") (pinfunction "2_2") (pintype "passive"))
      (node (ref "C69") (pin "2") (pinfunction "2_2") (pintype "passive"))
      (node (ref "C71") (pin "2") (pinfunction "2_2") (pintype "passive"))
      (node (ref "C72") (pin "2") (pinfunction "2_2") (pintype "passive"))
      (node (ref "C73") (pin "2") (pinfunction "2_2") (pintype "passive"))
      (node (ref "R43") (pin "1") (pinfunction "1_1") (pintype "passive"))
      (node (ref "R48") (pin "1") (pinfunction "1_1") (pintype "passive"))
      (node (ref "R52") (pin "1") (pinfunction "1_1") (pintype "passive"))
      (node (ref "R60") (pin "1") (pinfunction "1_1") (pintype "passive"))
      (node (ref "R61") (pin "1") (pinfunction "1_1") (pintype "passive"))
      (node (ref "U10") (pin "13") (pinfunction "PGND2_13") (pintype "power_in"))
      (node (ref "U10") (pin "17") (pinfunction "PowerPAD_17") (pintype "power_in"))
      (node (ref "U10") (pin "4") (pinfunction "PGND1_4") (pintype "power_in"))
      (node (ref "U10") (pin "8") (pinfunction "GND_8") (pintype "power_in"))
      (node (ref "U6") (pin "1") (pinfunction "PGND_1") (pintype "power_in"))
      (node (ref "U6") (pin "11") (pinfunction "GND_11") (pintype "power_in"))
      (node (ref "U9") (pin "13") (pinfunction "GND_13") (pintype "power_in"))
      (node (ref "U9") (pin "21") (pinfunction "Thermal_Pad_21") (pintype "power_in"))
      (node (ref "U9") (pin "3") (pinfunction "GND_3") (pintype "power_in"))
    )
    (net (code "2") (name "Net-(U6-BST)") (class "Default")
      (node (ref "C62") (pin "2") (pinfunction "2_2") (pintype "passive"))
      (node (ref "U6") (pin "7") (pinfunction "BST_7") (pintype "input"))
    )
    (net (code "3") (name "Net-(U6-FB)") (class "Default")
      (node (ref "R41") (pin "1") (pinfunction "1_1") (pintype "passive"))
      (node (ref "R43") (pin "2") (pinfunction "2_2") (pintype "passive"))
      (node (ref "U6") (pin "12") (pinfunction "FB_12") (pintype "input"))
    )
    (net (code "4") (name "Net-(U6-FSEL)") (class "Default")
      (node (ref "R42") (pin "2") (pinfunction "2_2") (pintype "passive"))
      (node (ref "U6") (pin "5") (pinfunction "FSEL_5") (pintype "input"))
    )
    (net (code "5") (name "Net-(U6-MODE)") (class "Default")
      (node (ref "R40") (pin "2") (pinfunction "2_2") (pintype "passive"))
      (node (ref "U6") (pin "4") (pinfunction "MODE_4") (pintype "input"))
    )
    (net (code "6") (name "Net-(U6-SS{slash}TR)") (class "Default")
      (node (ref "C173") (pin "1") (pinfunction "1_1") (pintype "passive"))
      (node (ref "U6") (pin "10") (pinfunction "SS/TR_10") (pintype "bidirectional"))
    )
    (net (code "7") (name "Net-(U6-SW)") (class "Default")
      (node (ref "C62") (pin "1") (pinfunction "1_1") (pintype "passive"))
      (node (ref "L1") (pin "1") (pinfunction "1_1") (pintype "passive"))
      (node (ref "U6") (pin "8") (pinfunction "SW_8") (pintype "output"))
    )
    (net (code "8") (name "Net-(U6-VCC)") (class "Default")
      (node (ref "C172") (pin "1") (pinfunction "1_1") (pintype "passive"))
      (node (ref "U6") (pin "9") (pinfunction "VCC_9") (pintype "power_in"))
    )
    (net (code "9") (name "Net-(U9-EN1)") (class "Default")
      (node (ref "R49") (pin "1") (pinfunction "1_1") (pintype "passive"))
      (node (ref "U9") (pin "20") (pinfunction "EN1_20") (pintype "input"))
    )
    (net (code "10") (name "Net-(U9-EN2)") (class "Default")
      (node (ref "R53") (pin "1") (pinfunction "1_1") (pintype "passive"))
      (node (ref "U9") (pin "6") (pinfunction "EN2_6") (pintype "input"))
    )
    (net (code "11") (name "Net-(U9-FB1)") (class "Default")
      (node (ref "C174") (pin "2") (pinfunction "2_2") (pintype "passive"))
      (node (ref "R46") (pin "2") (pinfunction "2_2") (pintype "passive"))
      (node (ref "R48") (pin "2") (pinfunction "2_2") (pintype "passive"))
      (node (ref "U9") (pin "16") (pinfunction "FB1_16") (pintype "input"))
    )
    (net (code "12") (name "Net-(U9-FB2)") (class "Default")
      (node (ref "C193") (pin "1") (pinfunction "1_1") (pintype "passive"))
      (node (ref "R50") (pin "1") (pinfunction "1_1") (pintype "passive"))
      (node (ref "R52") (pin "2") (pinfunction "2_2") (pintype "passive"))
      (node (ref "U9") (pin "10") (pinfunction "FB2_10") (pintype "input"))
    )
    (net (code "13") (name "Net-(U9-NR{slash}SS1)") (class "Default")
      (node (ref "C190") (pin "1") (pinfunction "1_1") (pintype "passive"))
      (node (ref "U9") (pin "19") (pinfunction "NR/SS1_19") (pintype "passive"))
    )
    (net (code "14") (name "Net-(U9-NR{slash}SS2)") (class "Default")
      (node (ref "C194") (pin "1") (pinfunction "1_1") (pintype "passive"))
      (node (ref "U9") (pin "7") (pinfunction "NR/SS2_7") (pintype "passive"))
    )
    (net (code "15") (name "Net-(U9-SS_CTRL1)") (class "Default")
      (node (ref "R47") (pin "1") (pinfunction "1_1") (pintype "passive"))
      (node (ref "U9") (pin "18") (pinfunction "SS_CTRL1_18") (pintype "passive"))
    )
    (net (code "16") (name "Net-(U9-SS_CTRL2)") (class "Default")
      (node (ref "R51") (pin "1") (pinfunction "1_1") (pintype "passive"))
      (node (ref "U9") (pin "8") (pinfunction "SS_CTRL2_8") (pintype "passive"))
    )
    (net (code "17") (name "Net-(U10-EN1)") (class "Default")
      (node (ref "R55") (pin "2") (pinfunction "2_2") (pintype "passive"))
      (node (ref "U10") (pin "5") (pinfunction "EN1_5") (pintype "input"))
    )
    (net (code "18") (name "Net-(U10-EN2)") (class "Default")
      (node (ref "R54") (pin "2") (pinfunction "2_2") (pintype "passive"))
      (node (ref "U10") (pin "12") (pinfunction "EN2_12") (pintype "input"))
    )
    (net (code "19") (name "Net-(U10-SS1)") (class "Default")
      (node (ref "C195") (pin "2") (pinfunction "2_2") (pintype "passive"))
      (node (ref "U10") (pin "6") (pinfunction "SS1_6") (pintype "output"))
    )
    (net (code "20") (name "Net-(U10-SS2)") (class "Default")
      (node (ref "C196") (pin "1") (pinfunction "1_1") (pintype "passive"))
      (node (ref "U10") (pin "11") (pinfunction "SS2_11") (pintype "output"))
    )
    (net (code "21") (name "Net-(U10-SW1)") (class "Default")
      (node (ref "C191") (pin "2") (pinfunction "2_2") (pintype "passive"))
      (node (ref "L21") (pin "2") (pinfunction "2_2") (pintype "passive"))
      (node (ref "U10") (pin "3") (pinfunction "SW1_3") (pintype "bidirectional"))
    )
    (net (code "22") (name "Net-(U10-SW2)") (class "Default")
      (node (ref "C192") (pin "1") (pinfunction "1_1") (pintype "passive"))
      (node (ref "L22") (pin "1") (pinfunction "1_1") (pintype "passive"))
      (node (ref "U10") (pin "14") (pinfunction "SW2_14") (pintype "bidirectional"))
    )
    (net (code "23") (name "Net-(U10-VBST1)") (class "Default")
      (node (ref "C191") (pin "1") (pinfunction "1_1") (pintype "passive"))
      (node (ref "U10") (pin "2") (pinfunction "VBST1_2") (pintype "passive"))
    )
    (net (code "24") (name "Net-(U10-VBST2)") (class "Default")
      (node (ref "C192") (pin "2") (pinfunction "2_2") (pintype "passive"))
      (node (ref "U10") (pin "15") (pinfunction "VBST2_15") (pintype "passive"))
    )
    (net (code "25") (name "Net-(U10-VFB1)") (class "Default")
      (node (ref "R57") (pin "2") (pinfunction "2_2") (pintype "passive"))
      (node (ref "R60") (pin "2") (pinfunction "2_2") (pintype "passive"))
      (node (ref "U10") (pin "7") (pinfunction "VFB1_7") (pintype "input"))
    )
    (net (code "26") (name "Net-(U10-VFB2)") (class "Default")
      (node (ref "R56") (pin "1") (pinfunction "1_1") (pintype "passive"))
      (node (ref "R61") (pin "2") (pinfunction "2_2") (pintype "passive"))
      (node (ref "U10") (pin "10") (pinfunction "VFB2_10") (pintype "input"))
    )
    (net (code "27") (name "Net-(U10-VREG5)") (class "Default")
      (node (ref "C209") (pin "2") (pinfunction "2_2") (pintype "passive"))
      (node (ref "U10") (pin "9") (pinfunction "VREG5_9") (pintype "power_in"))
    )
    (net (code "28") (name "P0V75") (class "Default")
      (node (ref "C169") (pin "1") (pinfunction "1_1") (pintype "passive"))
      (node (ref "C170") (pin "1") (pinfunction "1_1") (pintype "passive"))
      (node (ref "C171") (pin "1") (pinfunction "1_1") (pintype "passive"))
      (node (ref "C67") (pin "1") (pinfunction "1_1") (pintype "passive"))
      (node (ref "C68") (pin "1") (pinfunction "1_1") (pintype "passive"))
      (node (ref "C69") (pin "1") (pinfunction "1_1") (pintype "passive"))
      (node (ref "C71") (pin "1") (pinfunction "1_1") (pintype "passive"))
      (node (ref "C72") (pin "1") (pinfunction "1_1") (pintype "passive"))
      (node (ref "C73") (pin "1") (pinfunction "1_1") (pintype "passive"))
      (node (ref "L1") (pin "2") (pinfunction "2_2") (pintype "passive"))
      (node (ref "R41") (pin "2") (pinfunction "2_2") (pintype "passive"))
    )
    (net (code "29") (name "P0V75_EN") (class "Default")
      (node (ref "R37") (pin "2") (pinfunction "2_2") (pintype "passive"))
      (node (ref "U6") (pin "3") (pinfunction "EN_3") (pintype "input"))
    )
    (net (code "30") (name "P0V75_PG") (class "Default")
      (node (ref "R45") (pin "2") (pinfunction "2_2") (pintype "passive"))
      (node (ref "U6") (pin "6") (pinfunction "PG_6") (pintype "open_collector"))
    )
    (net (code "31") (name "P0V85") (class "Default")
      (node (ref "C193") (pin "2") (pinfunction "2_2") (pintype "passive"))
      (node (ref "C210") (pin "1") (pinfunction "1_1") (pintype "passive"))
      (node (ref "C211") (pin "1") (pinfunction "1_1") (pintype "passive"))
      (node (ref "C212") (pin "1") (pinfunction "1_1") (pintype "passive"))
      (node (ref "C213") (pin "1") (pinfunction "1_1") (pintype "passive"))
      (node (ref "R50") (pin "2") (pinfunction "2_2") (pintype "passive"))
      (node (ref "U9") (pin "11") (pinfunction "OUT2_11") (pintype "output"))
      (node (ref "U9") (pin "12") (pinfunction "OUT2_12") (pintype "output"))
    )
    (net (code "32") (name "P0V85_EN") (class "Default")
      (node (ref "R49") (pin "2") (pinfunction "2_2") (pintype "passive"))
    )
    (net (code "33") (name "P0V85_PG") (class "Default")
      (node (ref "R63") (pin "2") (pinfunction "2_2") (pintype "passive"))
      (node (ref "U9") (pin "9") (pinfunction "PG2_9") (pintype "open_collector"))
    )
    (net (code "34") (name "P1V2") (class "Default")
      (node (ref "C214") (pin "1") (pinfunction "1_1") (pintype "passive"))
      (node (ref "C216") (pin "1") (pinfunction "1_1") (pintype "passive"))
      (node (ref "C217") (pin "1") (pinfunction "1_1") (pintype "passive"))
      (node (ref "C218") (pin "1") (pinfunction "1_1") (pintype "passive"))
      (node (ref "C219") (pin "1") (pinfunction "1_1") (pintype "passive"))
      (node (ref "C220") (pin "1") (pinfunction "1_1") (pintype "passive"))
      (node (ref "C221") (pin "1") (pinfunction "1_1") (pintype "passive"))
      (node (ref "C222") (pin "1") (pinfunction "1_1") (pintype "passive"))
      (node (ref "C223") (pin "1") (pinfunction "1_1") (pintype "passive"))
      (node (ref "L21") (pin "1") (pinfunction "1_1") (pintype "passive"))
      (node (ref "R57") (pin "1") (pinfunction "1_1") (pintype "passive"))
    )
    (net (code "35") (name "P1V2_EN") (class "Default")
      (node (ref "R55") (pin "1") (pinfunction "1_1") (pintype "passive"))
    )
    (net (code "36") (name "P1V8") (class "Default")
      (node (ref "C215") (pin "1") (pinfunction "1_1") (pintype "passive"))
      (node (ref "C224") (pin "1") (pinfunction "1_1") (pintype "passive"))
      (node (ref "C225") (pin "1") (pinfunction "1_1") (pintype "passive"))
      (node (ref "C226") (pin "1") (pinfunction "1_1") (pintype "passive"))
      (node (ref "C227") (pin "1") (pinfunction "1_1") (pintype "passive"))
      (node (ref "C228") (pin "1") (pinfunction "1_1") (pintype "passive"))
      (node (ref "C229") (pin "1") (pinfunction "1_1") (pintype "passive"))
      (node (ref "C230") (pin "1") (pinfunction "1_1") (pintype "passive"))
      (node (ref "C231") (pin "1") (pinfunction "1_1") (pintype "passive"))
      (node (ref "L22") (pin "2") (pinfunction "2_2") (pintype "passive"))
      (node (ref "R56") (pin "2") (pinfunction "2_2") (pintype "passive"))
    )
    (net (code "37") (name "P1V8_CPU_ANA") (class "Default")
      (node (ref "C174") (pin "1") (pinfunction "1_1") (pintype "passive"))
      (node (ref "C205") (pin "1") (pinfunction "1_1") (pintype "passive"))
      (node (ref "C206") (pin "1") (pinfunction "1_1") (pintype "passive"))
      (node (ref "C207") (pin "1") (pinfunction "1_1") (pintype "passive"))
      (node (ref "C208") (pin "1") (pinfunction "1_1") (pintype "passive"))
      (node (ref "R46") (pin "1") (pinfunction "1_1") (pintype "passive"))
      (node (ref "U9") (pin "14") (pinfunction "OUT1_14") (pintype "output"))
      (node (ref "U9") (pin "15") (pinfunction "OUT1_15") (pintype "output"))
    )
    (net (code "38") (name "P1V8_CPU_ANA_EN") (class "Default")
      (node (ref "R53") (pin "2") (pinfunction "2_2") (pintype "passive"))
    )
    (net (code "39") (name "P1V8_CPU_ANA_PG") (class "Default")
      (node (ref "R65") (pin "2") (pinfunction "2_2") (pintype "passive"))
      (node (ref "U9") (pin "17") (pinfunction "PG1_17") (pintype "open_collector"))
    )
    (net (code "40") (name "P1V8_EN") (class "Default")
      (node (ref "R54") (pin "1") (pinfunction "1_1") (pintype "passive"))
    )
    (net (code "41") (name "P3V3") (class "Default")
      (node (ref "C197") (pin "1") (pinfunction "1_1") (pintype "passive"))
      (node (ref "C198") (pin "1") (pinfunction "1_1") (pintype "passive"))
      (node (ref "C199") (pin "1") (pinfunction "1_1") (pintype "passive"))
      (node (ref "C200") (pin "1") (pinfunction "1_1") (pintype "passive"))
      (node (ref "C201") (pin "1") (pinfunction "1_1") (pintype "passive"))
      (node (ref "C202") (pin "1") (pinfunction "1_1") (pintype "passive"))
      (node (ref "C203") (pin "1") (pinfunction "1_1") (pintype "passive"))
      (node (ref "C204") (pin "1") (pinfunction "1_1") (pintype "passive"))
      (node (ref "R37") (pin "1") (pinfunction "1_1") (pintype "passive"))
      (node (ref "R45") (pin "1") (pinfunction "1_1") (pintype "passive"))
      (node (ref "R47") (pin "2") (pinfunction "2_2") (pintype "passive"))
      (node (ref "R51") (pin "2") (pinfunction "2_2") (pintype "passive"))
      (node (ref "R63") (pin "1") (pinfunction "1_1") (pintype "passive"))
      (node (ref "R65") (pin "1") (pinfunction "1_1") (pintype "passive"))
      (node (ref "U9") (pin "1") (pinfunction "IN1_1") (pintype "input"))
      (node (ref "U9") (pin "2") (pinfunction "IN1_2") (pintype "input"))
      (node (ref "U9") (pin "4") (pinfunction "IN2_4") (pintype "input"))
      (node (ref "U9") (pin "5") (pinfunction "IN2_5") (pintype "input"))
    )
    (net (code "42") (name "P12V") (class "Default")
      (node (ref "C175") (pin "1") (pinfunction "1_1") (pintype "passive"))
      (node (ref "C176") (pin "1") (pinfunction "1_1") (pintype "passive"))
      (node (ref "C178") (pin "1") (pinfunction "1_1") (pintype "passive"))
      (node (ref "C179") (pin "1") (pinfunction "1_1") (pintype "passive"))
      (node (ref "C184") (pin "1") (pinfunction "1_1") (pintype "passive"))
      (node (ref "C185") (pin "1") (pinfunction "1_1") (pintype "passive"))
      (node (ref "C188") (pin "1") (pinfunction "1_1") (pintype "passive"))
      (node (ref "C189") (pin "1") (pinfunction "1_1") (pintype "passive"))
      (node (ref "C63") (pin "1") (pinfunction "1_1") (pintype "passive"))
      (node (ref "C64") (pin "1") (pinfunction "1_1") (pintype "passive"))
      (node (ref "C65") (pin "1") (pinfunction "1_1") (pintype "passive"))
      (node (ref "C66") (pin "1") (pinfunction "1_1") (pintype "passive"))
      (node (ref "R40") (pin "1") (pinfunction "1_1") (pintype "passive"))
      (node (ref "R42") (pin "1") (pinfunction "1_1") (pintype "passive"))
      (node (ref "U10") (pin "1") (pinfunction "VIN1_1") (pintype "power_in"))
      (node (ref "U10") (pin "16") (pinfunction "VIN2_16") (pintype "power_in"))
      (node (ref "U6") (pin "2") (pinfunction "VIN_2") (pintype "power_in"))
    )
  )
)
